# Teensy4-CANTool-Rev3.net
KiCad netlist of a schematic drawn in Altium Designer
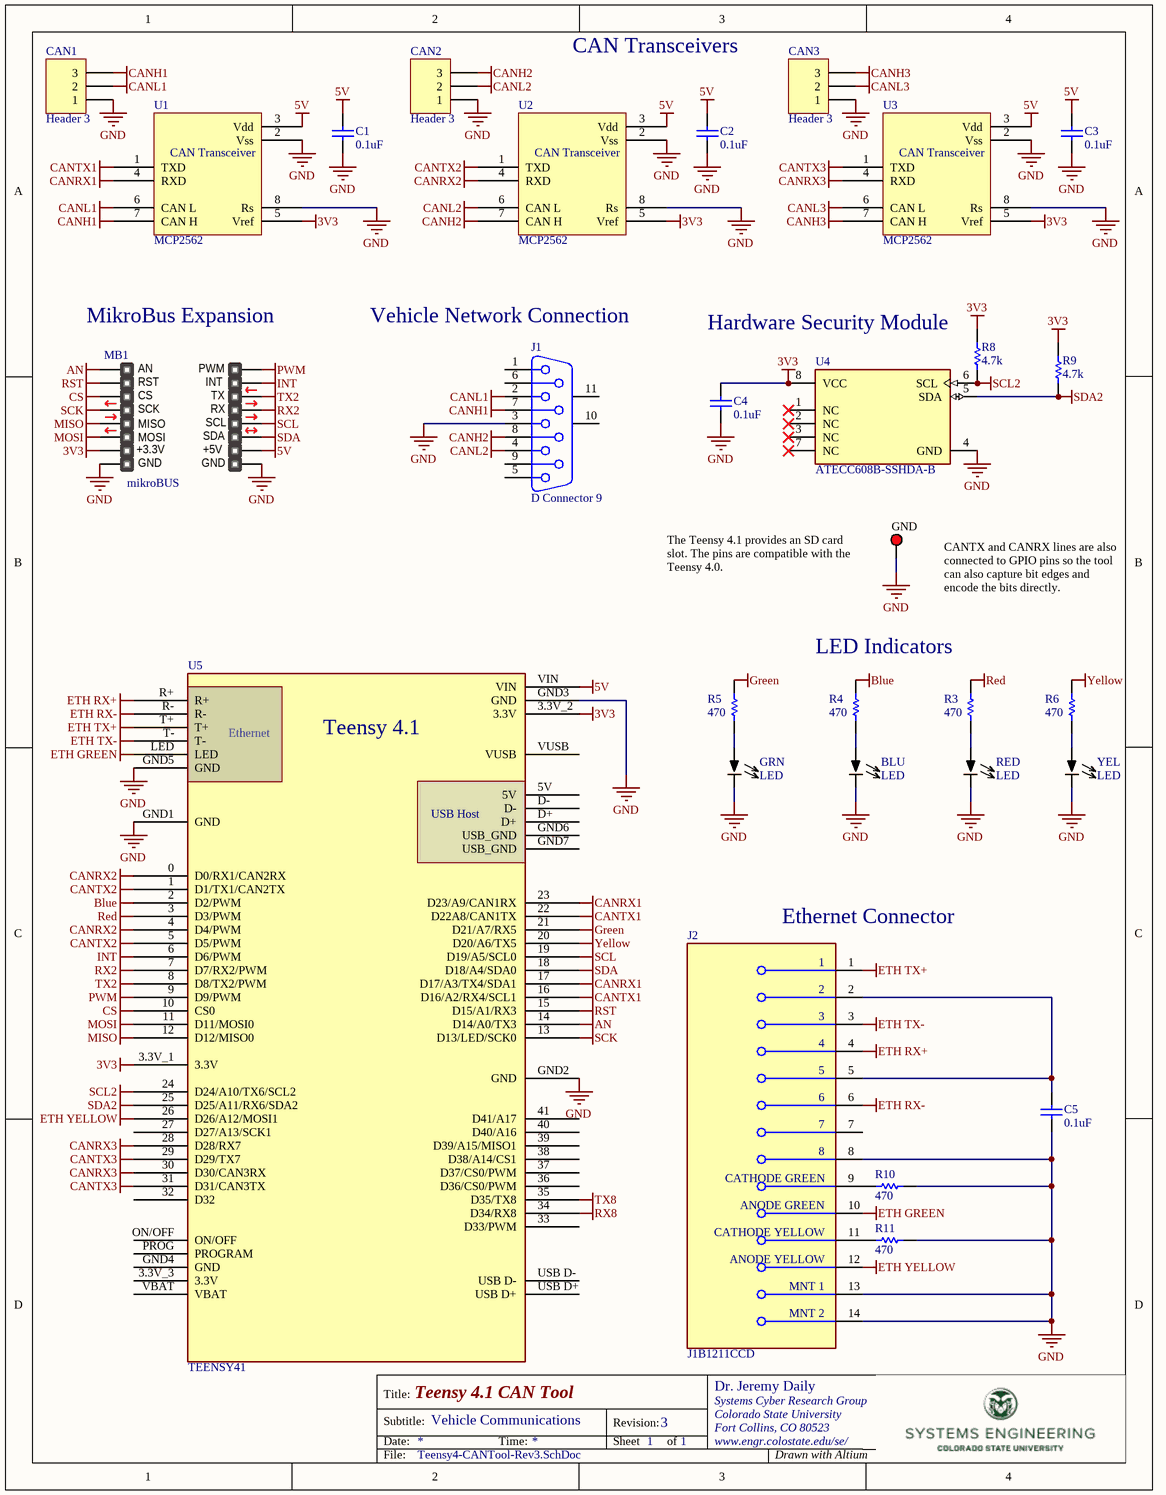
[diagram p0: Teensy4-CANTool-Rev3.SchDoc]

(export (version "E")
  (design (tool "Eeschema 10.0.6"))
  (components
    (comp (ref "BLU")
      (value "LED")
      (footprint "LED - 5mm Through Hole")
      (description "Blue 470nm LED Indication - Discrete 3.2V Radial")
      (fields (field (name "MANUFACTURER") "Würth Elektronik") (field (name "PARTNUMBER") "151051BS04000"))
      (libsource (lib "Custom Parts") (part "LED"))
    )
    (comp (ref "C1")
      (value "0.1uF")
      (footprint "CAPR5-4X5")
      (description "0.1µF ±10% 50V Ceramic Capacitor X7R 0603 (1608 Metric)")
      (fields
        (field (name "MANUFACTURER") "Vishay Beyschlag/Draloric/BC Components")
        (field (name "PARTNUMBER") "K104K15X7RF53H5")
      )
      (libsource (lib "SSS Schematic Library") (part "Cap"))
    )
    (comp (ref "C2")
      (value "0.1uF")
      (footprint "CAPR5-4X5")
      (description "0.1µF ±10% 50V Ceramic Capacitor X7R 0603 (1608 Metric)")
      (fields
        (field (name "MANUFACTURER") "Vishay Beyschlag/Draloric/BC Components")
        (field (name "PARTNUMBER") "K104K15X7RF53H5")
      )
      (libsource (lib "SSS Schematic Library") (part "Cap"))
    )
    (comp (ref "C3")
      (value "0.1uF")
      (footprint "CAPR5-4X5")
      (description "0.1µF ±10% 50V Ceramic Capacitor X7R 0603 (1608 Metric)")
      (fields
        (field (name "MANUFACTURER") "Vishay Beyschlag/Draloric/BC Components")
        (field (name "PARTNUMBER") "K104K15X7RF53H5")
      )
      (libsource (lib "SSS Schematic Library") (part "Cap"))
    )
    (comp (ref "C4")
      (value "0.1uF")
      (footprint "CAPR5-4X5")
      (description "0.1µF ±10% 50V Ceramic Capacitor X7R 0603 (1608 Metric)")
      (fields
        (field (name "MANUFACTURER") "Vishay Beyschlag/Draloric/BC Components")
        (field (name "PARTNUMBER") "K104K15X7RF53H5")
      )
      (libsource (lib "SSS Schematic Library") (part "Cap"))
    )
    (comp (ref "C5")
      (value "0.1uF")
      (footprint "CAPR5-4X5")
      (description "0.1µF ±10% 50V Ceramic Capacitor X7R 0603 (1608 Metric)")
      (fields
        (field (name "MANUFACTURER") "Vishay Beyschlag/Draloric/BC Components")
        (field (name "PARTNUMBER") "K104K15X7RF53H5")
      )
      (libsource (lib "SSS Schematic Library") (part "Cap"))
    )
    (comp (ref "CAN1")
      (value "Header 3")
      (footprint "PCB Terminal Block - 3")
      (description "Header, 3-Pin")
      (fields (field (name "MANUFACTURER") "Phoenix Contact") (field (name "PARTNUMBER") "1935174"))
      (libsource (lib "Miscellaneous Connectors") (part "Header 3"))
    )
    (comp (ref "CAN2")
      (value "Header 3")
      (footprint "PCB Terminal Block - 3")
      (description "Header, 3-Pin")
      (fields (field (name "MANUFACTURER") "Phoenix Contact") (field (name "PARTNUMBER") "1935174"))
      (libsource (lib "Miscellaneous Connectors") (part "Header 3"))
    )
    (comp (ref "CAN3")
      (value "Header 3")
      (footprint "PCB Terminal Block - 3")
      (description "Header, 3-Pin")
      (fields (field (name "MANUFACTURER") "Phoenix Contact") (field (name "PARTNUMBER") "1935174"))
      (libsource (lib "Miscellaneous Connectors") (part "Header 3"))
    )
    (comp (ref "GND")
      (value "5010")
      (footprint "KSTN-5010_V")
      (description "Interconnection Device")
      (libsource (lib "CSU Systems Cyber") (part "TESTPOINT_RED"))
    )
    (comp (ref "GRN")
      (value "LED")
      (footprint "LED - 5mm Through Hole")
      (description "Green 572nm LED Indication - Discrete 2.1V Radial")
      (fields (field (name "MANUFACTURER") "Würth Elektronik") (field (name "PARTNUMBER") "151051VS04000"))
      (libsource (lib "Custom Parts") (part "LED"))
    )
    (comp (ref "J1")
      (value "D Connector 9")
      (footprint "DSUB1.385-2H9")
      (description "CONN D-SUB PLUG 9POS R/A SLDR")
      (fields
        (field (name "MANUFACTURER") "Assmann WSW Components")
        (field (name "PARTNUMBER") "A-DS 09 A/KG-T2S")
      )
      (libsource (lib "Miscellaneous Connectors") (part "D Connector 9"))
    )
    (comp (ref "J2")
      (value "J1B1211CCD")
      (footprint "FP-J1B1211CCD-MFG")
      (description "CONN JACK 1PORT 100 BASE-T PCB")
      (libsource (lib "Altium Content Vault") (part "043a9053fb366fe6dc2bf5dbfb72c80"))
    )
    (comp (ref "MB1")
      (value "mikroBUS")
      (footprint "mikroBUS - Midi")
      (description "mikroBUS compatible add-on board")
      (libsource (lib "mikroBUS_Add-on_standard") (part "mikroBUS compatible add-on board"))
    )
    (comp (ref "R3")
      (value "470")
      (footprint "AXIAL-0.4")
      (description "470 Ohms ±5% 0.25W, 1/4W Through Hole Resistor Axial Carbon Film")
      (fields (field (name "MANUFACTURER") "YAGEO") (field (name "PARTNUMBER") "CFR-25JB-52-470R"))
      (libsource (lib "Miscellaneous Devices") (part "Res1"))
    )
    (comp (ref "R4")
      (value "470")
      (footprint "AXIAL-0.4")
      (description "470 Ohms ±5% 0.25W, 1/4W Through Hole Resistor Axial Carbon Film")
      (fields (field (name "MANUFACTURER") "YAGEO") (field (name "PARTNUMBER") "CFR-25JB-52-470R"))
      (libsource (lib "Miscellaneous Devices") (part "Res1"))
    )
    (comp (ref "R5")
      (value "470")
      (footprint "AXIAL-0.4")
      (description "470 Ohms ±5% 0.25W, 1/4W Through Hole Resistor Axial Carbon Film")
      (fields (field (name "MANUFACTURER") "YAGEO") (field (name "PARTNUMBER") "CFR-25JB-52-470R"))
      (libsource (lib "Miscellaneous Devices") (part "Res1"))
    )
    (comp (ref "R6")
      (value "470")
      (footprint "AXIAL-0.4")
      (description "470 Ohms ±5% 0.25W, 1/4W Through Hole Resistor Axial Carbon Film")
      (fields (field (name "MANUFACTURER") "YAGEO") (field (name "PARTNUMBER") "CFR-25JB-52-470R"))
      (libsource (lib "Miscellaneous Devices") (part "Res1"))
    )
    (comp (ref "R8")
      (value "4.7k")
      (footprint "RESA60-630X240")
      (description "Axial Resistor, 47.5 KOhm, +/- 1%, 0.25 W, -55 to 155 degC, 2-Pin THD, RoHS, Bulk")
      (fields (field (name "TOLERANCE") "20%"))
      (libsource (lib "Altium Content Vault") (part "RES-2"))
    )
    (comp (ref "R9")
      (value "4.7k")
      (footprint "RESA60-630X240")
      (description "Axial Resistor, 47.5 KOhm, +/- 1%, 0.25 W, -55 to 155 degC, 2-Pin THD, RoHS, Bulk")
      (fields (field (name "TOLERANCE") "20%"))
      (libsource (lib "Altium Content Vault") (part "RES-2"))
    )
    (comp (ref "R10")
      (value "470")
      (footprint "AXIAL-0.4")
      (description "470 Ohms ±5% 0.25W, 1/4W Through Hole Resistor Axial Carbon Film")
      (fields (field (name "MANUFACTURER") "YAGEO") (field (name "PARTNUMBER") "CFR-25JB-52-470R"))
      (libsource (lib "Miscellaneous Devices") (part "Res1"))
    )
    (comp (ref "R11")
      (value "470")
      (footprint "axial-0.4")
      (description "470 Ohms ±5% 0.25W, 1/4W Through Hole Resistor Axial Carbon Film")
      (fields (field (name "MANUFACTURER") "YAGEO") (field (name "PARTNUMBER") "CFR-25JB-52-470R"))
      (libsource (lib "Miscellaneous Devices") (part "Res1"))
    )
    (comp (ref "RED")
      (value "LED")
      (footprint "LED - 5mm Through Hole")
      (description "Red 645nm LED Indication - Discrete 2.1V Radial")
      (fields (field (name "MANUFACTURER") "Würth Elektronik") (field (name "PARTNUMBER") "151051RS11000"))
      (libsource (lib "Custom Parts") (part "LED"))
    )
    (comp (ref "U1")
      (value "MCP2562")
      (footprint "DIP8")
      (description "1/1 Transceiver CANbus 8-PDIP")
      (fields
        (field (name "MANUFACTURER") "Microchip Technology")
        (field (name "PARTNUMBER") "MCP2562FD-E/P")
      )
      (libsource (lib "SSS Integrated Library") (part "MCP2551"))
    )
    (comp (ref "U2")
      (value "MCP2562")
      (footprint "DIP8")
      (description "1/1 Transceiver CANbus 8-PDIP")
      (fields
        (field (name "MANUFACTURER") "Microchip Technology")
        (field (name "PARTNUMBER") "MCP2562FD-E/P")
      )
      (libsource (lib "SSS Integrated Library") (part "MCP2551"))
    )
    (comp (ref "U3")
      (value "MCP2562")
      (footprint "DIP8")
      (description "1/1 Transceiver CANbus 8-PDIP")
      (fields
        (field (name "MANUFACTURER") "Microchip Technology")
        (field (name "PARTNUMBER") "MCP2562FD-E/P")
      )
      (libsource (lib "SSS Integrated Library") (part "MCP2551"))
    )
    (comp (ref "U4")
      (value "ATECC608B-SSHDA-B")
      (footprint "FP-C04-057-SWB-IPC_C")
      (description "IC AUTHENTICATION CHIP")
      (libsource (lib "Altium Content Vault") (part "1f7132c691f143be83197a8e1c9b4e2"))
    )
    (comp (ref "U5")
      (value "TEENSY41")
      (footprint "MODULE_DEV-16771")
      (description "PJRC Teensy 4.1 Development Board")
      (libsource (lib "CSU Systems Cyber") (part "Teensy 4.1"))
    )
    (comp (ref "YEL")
      (value "LED")
      (footprint "LED - 5mm Through Hole")
      (description "Yellow 590nm LED Indication - Discrete 2V Radial")
      (fields (field (name "MANUFACTURER") "Würth Elektronik") (field (name "PARTNUMBER") "151051YS04000"))
      (libsource (lib "Custom Parts") (part "LED"))
    )
  )
  (nets
    (net (code "1") (name "3V3") (class "Default")
      (node (ref "C4") (pin "2") (pinfunction "2_2") (pintype "passive"))
      (node (ref "MB1") (pin "7") (pinfunction "3.3V_7") (pintype "passive"))
      (node (ref "R8") (pin "2") (pinfunction "2_2") (pintype "passive"))
      (node (ref "R9") (pin "2") (pinfunction "2_2") (pintype "passive"))
      (node (ref "U1") (pin "5") (pinfunction "Vref_5") (pintype "passive"))
      (node (ref "U2") (pin "5") (pinfunction "Vref_5") (pintype "passive"))
      (node (ref "U3") (pin "5") (pinfunction "Vref_5") (pintype "passive"))
      (node (ref "U4") (pin "8") (pinfunction "VCC_8") (pintype "power_in"))
      (node (ref "U5") (pin "3.3V_1") (pinfunction "3.3V_3.3V_1") (pintype "passive"))
      (node (ref "U5") (pin "3.3V_2") (pinfunction "3.3V_3.3V_2") (pintype "power_in"))
    )
    (net (code "2") (name "5V") (class "Default")
      (node (ref "C1") (pin "2") (pinfunction "2_2") (pintype "passive"))
      (node (ref "C2") (pin "2") (pinfunction "2_2") (pintype "passive"))
      (node (ref "C3") (pin "2") (pinfunction "2_2") (pintype "passive"))
      (node (ref "MB1") (pin "10") (pinfunction "5V_10") (pintype "passive"))
      (node (ref "U1") (pin "3") (pinfunction "Vdd_3") (pintype "passive"))
      (node (ref "U2") (pin "3") (pinfunction "Vdd_3") (pintype "passive"))
      (node (ref "U3") (pin "3") (pinfunction "Vdd_3") (pintype "passive"))
      (node (ref "U5") (pin "VIN") (pinfunction "VIN_VIN") (pintype "passive"))
    )
    (net (code "3") (name "AN") (class "Default")
      (node (ref "MB1") (pin "1") (pinfunction "AN_1") (pintype "passive"))
      (node (ref "U5") (pin "14") (pinfunction "D14/A0/TX3_14") (pintype "passive"))
    )
    (net (code "4") (name "Blue") (class "Default")
      (node (ref "R4") (pin "2") (pinfunction "2_2") (pintype "passive"))
      (node (ref "U5") (pin "2") (pinfunction "D2/PWM_2") (pintype "passive"))
    )
    (net (code "5") (name "CANH1") (class "Default")
      (node (ref "CAN1") (pin "3") (pinfunction "3_3") (pintype "passive"))
      (node (ref "J1") (pin "7") (pinfunction "7_7") (pintype "passive"))
      (node (ref "U1") (pin "7") (pinfunction "CAN_H_7") (pintype "passive"))
    )
    (net (code "6") (name "CANH2") (class "Default")
      (node (ref "CAN2") (pin "3") (pinfunction "3_3") (pintype "passive"))
      (node (ref "J1") (pin "8") (pinfunction "8_8") (pintype "passive"))
      (node (ref "U2") (pin "7") (pinfunction "CAN_H_7") (pintype "passive"))
    )
    (net (code "7") (name "CANH3") (class "Default")
      (node (ref "CAN3") (pin "3") (pinfunction "3_3") (pintype "passive"))
      (node (ref "U3") (pin "7") (pinfunction "CAN_H_7") (pintype "passive"))
    )
    (net (code "8") (name "CANL1") (class "Default")
      (node (ref "CAN1") (pin "2") (pinfunction "2_2") (pintype "passive"))
      (node (ref "J1") (pin "2") (pinfunction "2_2") (pintype "passive"))
      (node (ref "U1") (pin "6") (pinfunction "CAN_L_6") (pintype "passive"))
    )
    (net (code "9") (name "CANL2") (class "Default")
      (node (ref "CAN2") (pin "2") (pinfunction "2_2") (pintype "passive"))
      (node (ref "J1") (pin "4") (pinfunction "4_4") (pintype "passive"))
      (node (ref "U2") (pin "6") (pinfunction "CAN_L_6") (pintype "passive"))
    )
    (net (code "10") (name "CANL3") (class "Default")
      (node (ref "CAN3") (pin "2") (pinfunction "2_2") (pintype "passive"))
      (node (ref "U3") (pin "6") (pinfunction "CAN_L_6") (pintype "passive"))
    )
    (net (code "11") (name "CANRX1") (class "Default")
      (node (ref "U1") (pin "4") (pinfunction "RXD_4") (pintype "passive"))
      (node (ref "U5") (pin "17") (pinfunction "D17/A3/TX4/SDA1_17") (pintype "passive"))
      (node (ref "U5") (pin "23") (pinfunction "D23/A9/CAN1RX_23") (pintype "passive"))
    )
    (net (code "12") (name "CANRX2") (class "Default")
      (node (ref "U2") (pin "4") (pinfunction "RXD_4") (pintype "passive"))
      (node (ref "U5") (pin "0") (pinfunction "D0/RX1/CAN2RX_0") (pintype "passive"))
      (node (ref "U5") (pin "4") (pinfunction "D4/PWM_4") (pintype "passive"))
    )
    (net (code "13") (name "CANRX3") (class "Default")
      (node (ref "U3") (pin "4") (pinfunction "RXD_4") (pintype "passive"))
      (node (ref "U5") (pin "28") (pinfunction "D28/RX7_28") (pintype "passive"))
      (node (ref "U5") (pin "30") (pinfunction "D30/CAN3RX_30") (pintype "passive"))
    )
    (net (code "14") (name "CANTX1") (class "Default")
      (node (ref "U1") (pin "1") (pinfunction "TXD_1") (pintype "passive"))
      (node (ref "U5") (pin "16") (pinfunction "D16/A2/RX4/SCL1_16") (pintype "passive"))
      (node (ref "U5") (pin "22") (pinfunction "D22A8/CAN1TX_22") (pintype "passive"))
    )
    (net (code "15") (name "CANTX2") (class "Default")
      (node (ref "U2") (pin "1") (pinfunction "TXD_1") (pintype "passive"))
      (node (ref "U5") (pin "1") (pinfunction "D1/TX1/CAN2TX_1") (pintype "passive"))
      (node (ref "U5") (pin "5") (pinfunction "D5/PWM_5") (pintype "passive"))
    )
    (net (code "16") (name "CANTX3") (class "Default")
      (node (ref "U3") (pin "1") (pinfunction "TXD_1") (pintype "passive"))
      (node (ref "U5") (pin "29") (pinfunction "D29/TX7_29") (pintype "passive"))
      (node (ref "U5") (pin "31") (pinfunction "D31/CAN3TX_31") (pintype "passive"))
    )
    (net (code "17") (name "CS") (class "Default")
      (node (ref "MB1") (pin "3") (pinfunction "CS_3") (pintype "passive"))
      (node (ref "U5") (pin "10") (pinfunction "CS0_10") (pintype "passive"))
    )
    (net (code "18") (name "ETH GREEN") (class "Default")
      (node (ref "J2") (pin "10") (pinfunction "ANODE_GREEN_10") (pintype "passive"))
      (node (ref "U5") (pin "LED") (pinfunction "LED_LED") (pintype "passive"))
    )
    (net (code "19") (name "ETH RX+") (class "Default")
      (node (ref "J2") (pin "4") (pinfunction "4_4") (pintype "passive"))
      (node (ref "U5") (pin "R+") (pinfunction "R+_R+") (pintype "passive"))
    )
    (net (code "20") (name "ETH RX-") (class "Default")
      (node (ref "J2") (pin "6") (pinfunction "6_6") (pintype "passive"))
      (node (ref "U5") (pin "R-") (pinfunction "R-_R-") (pintype "passive"))
    )
    (net (code "21") (name "ETH TX+") (class "Default")
      (node (ref "J2") (pin "1") (pinfunction "1_1") (pintype "passive"))
      (node (ref "U5") (pin "T+") (pinfunction "T+_T+") (pintype "passive"))
    )
    (net (code "22") (name "ETH TX-") (class "Default")
      (node (ref "J2") (pin "3") (pinfunction "3_3") (pintype "passive"))
      (node (ref "U5") (pin "T-") (pinfunction "T-_T-") (pintype "passive"))
    )
    (net (code "23") (name "ETH YELLOW") (class "Default")
      (node (ref "J2") (pin "12") (pinfunction "ANODE_YELLOW_12") (pintype "passive"))
      (node (ref "U5") (pin "26") (pinfunction "D26/A12/MOSI1_26") (pintype "passive"))
    )
    (net (code "24") (name "GND") (class "Default")
      (node (ref "BLU") (pin "2") (pinfunction "C_2") (pintype "passive"))
      (node (ref "C1") (pin "1") (pinfunction "1_1") (pintype "passive"))
      (node (ref "C2") (pin "1") (pinfunction "1_1") (pintype "passive"))
      (node (ref "C3") (pin "1") (pinfunction "1_1") (pintype "passive"))
      (node (ref "C4") (pin "1") (pinfunction "1_1") (pintype "passive"))
      (node (ref "C5") (pin "1") (pinfunction "1_1") (pintype "passive"))
      (node (ref "CAN1") (pin "1") (pinfunction "1_1") (pintype "passive"))
      (node (ref "CAN2") (pin "1") (pinfunction "1_1") (pintype "passive"))
      (node (ref "CAN3") (pin "1") (pinfunction "1_1") (pintype "passive"))
      (node (ref "GND") (pin "1") (pinfunction "1_1") (pintype "passive"))
      (node (ref "GRN") (pin "2") (pinfunction "C_2") (pintype "passive"))
      (node (ref "J1") (pin "3") (pinfunction "3_3") (pintype "passive"))
      (node (ref "J2") (pin "13") (pinfunction "MNT_1_13") (pintype "passive"))
      (node (ref "J2") (pin "14") (pinfunction "MNT_2_14") (pintype "passive"))
      (node (ref "J2") (pin "8") (pinfunction "8_8") (pintype "passive"))
      (node (ref "MB1") (pin "8") (pinfunction "GND_8") (pintype "passive"))
      (node (ref "MB1") (pin "9") (pinfunction "GND_9") (pintype "passive"))
      (node (ref "R10") (pin "1") (pinfunction "1_1") (pintype "passive"))
      (node (ref "R11") (pin "1") (pinfunction "1_1") (pintype "passive"))
      (node (ref "RED") (pin "2") (pinfunction "C_2") (pintype "passive"))
      (node (ref "U1") (pin "2") (pinfunction "Vss_2") (pintype "passive"))
      (node (ref "U1") (pin "8") (pinfunction "Rs_8") (pintype "passive"))
      (node (ref "U2") (pin "2") (pinfunction "Vss_2") (pintype "passive"))
      (node (ref "U2") (pin "8") (pinfunction "Rs_8") (pintype "passive"))
      (node (ref "U3") (pin "2") (pinfunction "Vss_2") (pintype "passive"))
      (node (ref "U3") (pin "8") (pinfunction "Rs_8") (pintype "passive"))
      (node (ref "U4") (pin "4") (pinfunction "GND_4") (pintype "power_in"))
      (node (ref "U5") (pin "GND1") (pinfunction "GND_GND1") (pintype "passive"))
      (node (ref "U5") (pin "GND2") (pinfunction "GND_GND2") (pintype "power_in"))
      (node (ref "U5") (pin "GND3") (pinfunction "GND_GND3") (pintype "power_in"))
      (node (ref "U5") (pin "GND5") (pinfunction "GND_GND5") (pintype "passive"))
      (node (ref "YEL") (pin "2") (pinfunction "C_2") (pintype "passive"))
    )
    (net (code "25") (name "Green") (class "Default")
      (node (ref "R5") (pin "2") (pinfunction "2_2") (pintype "passive"))
      (node (ref "U5") (pin "21") (pinfunction "D21/A7/RX5_21") (pintype "passive"))
    )
    (net (code "26") (name "INT") (class "Default")
      (node (ref "MB1") (pin "15") (pinfunction "INT_15") (pintype "passive"))
      (node (ref "U5") (pin "6") (pinfunction "D6/PWM_6") (pintype "passive"))
    )
    (net (code "27") (name "MISO") (class "Default")
      (node (ref "MB1") (pin "5") (pinfunction "MISO_5") (pintype "passive"))
      (node (ref "U5") (pin "12") (pinfunction "D12/MISO0_12") (pintype "passive"))
    )
    (net (code "28") (name "MOSI") (class "Default")
      (node (ref "MB1") (pin "6") (pinfunction "MOSI_6") (pintype "passive"))
      (node (ref "U5") (pin "11") (pinfunction "D11/MOSI0_11") (pintype "passive"))
    )
    (net (code "29") (name "Net-(BLU-A)") (class "Default")
      (node (ref "BLU") (pin "1") (pinfunction "A_1") (pintype "passive"))
      (node (ref "R4") (pin "1") (pinfunction "1_1") (pintype "passive"))
    )
    (net (code "30") (name "Net-(C5-Pad2)") (class "Default")
      (node (ref "C5") (pin "2") (pinfunction "2_2") (pintype "passive"))
      (node (ref "J2") (pin "2") (pinfunction "2_2") (pintype "passive"))
      (node (ref "J2") (pin "5") (pinfunction "5_5") (pintype "passive"))
    )
    (net (code "31") (name "Net-(GRN-A)") (class "Default")
      (node (ref "GRN") (pin "1") (pinfunction "A_1") (pintype "passive"))
      (node (ref "R5") (pin "1") (pinfunction "1_1") (pintype "passive"))
    )
    (net (code "32") (name "Net-(J2-CATHODE_GREEN)") (class "Default")
      (node (ref "J2") (pin "9") (pinfunction "CATHODE_GREEN_9") (pintype "passive"))
      (node (ref "R10") (pin "2") (pinfunction "2_2") (pintype "passive"))
    )
    (net (code "33") (name "Net-(J2-CATHODE_YELLOW)") (class "Default")
      (node (ref "J2") (pin "11") (pinfunction "CATHODE_YELLOW_11") (pintype "passive"))
      (node (ref "R11") (pin "2") (pinfunction "2_2") (pintype "passive"))
    )
    (net (code "34") (name "Net-(RED-A)") (class "Default")
      (node (ref "R3") (pin "1") (pinfunction "1_1") (pintype "passive"))
      (node (ref "RED") (pin "1") (pinfunction "A_1") (pintype "passive"))
    )
    (net (code "35") (name "Net-(YEL-A)") (class "Default")
      (node (ref "R6") (pin "1") (pinfunction "1_1") (pintype "passive"))
      (node (ref "YEL") (pin "1") (pinfunction "A_1") (pintype "passive"))
    )
    (net (code "36") (name "PWM") (class "Default")
      (node (ref "MB1") (pin "16") (pinfunction "PWM_16") (pintype "passive"))
      (node (ref "U5") (pin "9") (pinfunction "D9/PWM_9") (pintype "passive"))
    )
    (net (code "37") (name "RST") (class "Default")
      (node (ref "MB1") (pin "2") (pinfunction "RST_2") (pintype "passive"))
      (node (ref "U5") (pin "15") (pinfunction "D15/A1/RX3_15") (pintype "passive"))
    )
    (net (code "38") (name "RX2") (class "Default")
      (node (ref "MB1") (pin "13") (pinfunction "TX_13") (pintype "passive"))
      (node (ref "U5") (pin "7") (pinfunction "D7/RX2/PWM_7") (pintype "passive"))
    )
    (net (code "39") (name "RX8") (class "Default")
      (node (ref "U5") (pin "34") (pinfunction "D34/RX8_34") (pintype "passive"))
    )
    (net (code "40") (name "Red") (class "Default")
      (node (ref "R3") (pin "2") (pinfunction "2_2") (pintype "passive"))
      (node (ref "U5") (pin "3") (pinfunction "D3/PWM_3") (pintype "passive"))
    )
    (net (code "41") (name "SCK") (class "Default")
      (node (ref "MB1") (pin "4") (pinfunction "SCK_4") (pintype "passive"))
      (node (ref "U5") (pin "13") (pinfunction "D13/LED/SCK0_13") (pintype "passive"))
    )
    (net (code "42") (name "SCL") (class "Default")
      (node (ref "MB1") (pin "12") (pinfunction "SCL_12") (pintype "passive"))
      (node (ref "U5") (pin "19") (pinfunction "D19/A5/SCL0_19") (pintype "passive"))
    )
    (net (code "43") (name "SCL2") (class "Default")
      (node (ref "R8") (pin "1") (pinfunction "1_1") (pintype "passive"))
      (node (ref "U4") (pin "6") (pinfunction "SCL_6") (pintype "input"))
      (node (ref "U5") (pin "24") (pinfunction "D24/A10/TX6/SCL2_24") (pintype "passive"))
    )
    (net (code "44") (name "SDA") (class "Default")
      (node (ref "MB1") (pin "11") (pinfunction "SDA_11") (pintype "passive"))
      (node (ref "U5") (pin "18") (pinfunction "D18/A4/SDA0_18") (pintype "passive"))
    )
    (net (code "45") (name "SDA2") (class "Default")
      (node (ref "R9") (pin "1") (pinfunction "1_1") (pintype "passive"))
      (node (ref "U4") (pin "5") (pinfunction "SDA_5") (pintype "bidirectional"))
      (node (ref "U5") (pin "25") (pinfunction "D25/A11/RX6/SDA2_25") (pintype "passive"))
    )
    (net (code "46") (name "TX2") (class "Default")
      (node (ref "MB1") (pin "14") (pinfunction "RX_14") (pintype "passive"))
      (node (ref "U5") (pin "8") (pinfunction "D8/TX2/PWM_8") (pintype "passive"))
    )
    (net (code "47") (name "TX8") (class "Default")
      (node (ref "U5") (pin "35") (pinfunction "D35/TX8_35") (pintype "passive"))
    )
    (net (code "48") (name "Yellow") (class "Default")
      (node (ref "R6") (pin "2") (pinfunction "2_2") (pintype "passive"))
      (node (ref "U5") (pin "20") (pinfunction "D20/A6/TX5_20") (pintype "passive"))
    )
    (net (code "49") (name "unconnected-(J1-MH1-Pad10)") (class "Default")
      (node (ref "J1") (pin "10") (pinfunction "MH1_10") (pintype "passive"))
    )
    (net (code "50") (name "unconnected-(J1-MH2-Pad11)") (class "Default")
      (node (ref "J1") (pin "11") (pinfunction "MH2_11") (pintype "passive"))
    )
    (net (code "51") (name "unconnected-(J1-Pad1)") (class "Default")
      (node (ref "J1") (pin "1") (pinfunction "1_1") (pintype "passive"))
    )
    (net (code "52") (name "unconnected-(J1-Pad5)") (class "Default")
      (node (ref "J1") (pin "5") (pinfunction "5_5") (pintype "passive"))
    )
    (net (code "53") (name "unconnected-(J1-Pad6)") (class "Default")
      (node (ref "J1") (pin "6") (pinfunction "6_6") (pintype "passive"))
    )
    (net (code "54") (name "unconnected-(J1-Pad9)") (class "Default")
      (node (ref "J1") (pin "9") (pinfunction "9_9") (pintype "passive"))
    )
    (net (code "55") (name "unconnected-(J2-Pad7)") (class "Default")
      (node (ref "J2") (pin "7") (pinfunction "7_7") (pintype "passive"))
    )
    (net (code "56") (name "unconnected-(U4-NC-Pad1)") (class "Default")
      (node (ref "U4") (pin "1") (pinfunction "NC_1") (pintype "passive+no_connect"))
    )
    (net (code "57") (name "unconnected-(U4-NC-Pad2)") (class "Default")
      (node (ref "U4") (pin "2") (pinfunction "NC_2") (pintype "passive+no_connect"))
    )
    (net (code "58") (name "unconnected-(U4-NC-Pad3)") (class "Default")
      (node (ref "U4") (pin "3") (pinfunction "NC_3") (pintype "passive+no_connect"))
    )
    (net (code "59") (name "unconnected-(U4-NC-Pad7)") (class "Default")
      (node (ref "U4") (pin "7") (pinfunction "NC_7") (pintype "passive+no_connect"))
    )
    (net (code "60") (name "unconnected-(U5-3.3V-Pad3.3V_3)") (class "Default")
      (node (ref "U5") (pin "3.3V_3") (pinfunction "3.3V_3.3V_3") (pintype "passive"))
    )
    (net (code "61") (name "unconnected-(U5-D27{slash}A13{slash}SCK1-Pad27)") (class "Default")
      (node (ref "U5") (pin "27") (pinfunction "D27/A13/SCK1_27") (pintype "passive"))
    )
    (net (code "62") (name "unconnected-(U5-D32-Pad32)") (class "Default")
      (node (ref "U5") (pin "32") (pinfunction "D32_32") (pintype "passive"))
    )
    (net (code "63") (name "unconnected-(U5-D33{slash}PWM-Pad33)") (class "Default")
      (node (ref "U5") (pin "33") (pinfunction "D33/PWM_33") (pintype "passive"))
    )
    (net (code "64") (name "unconnected-(U5-D36{slash}CS0{slash}PWM-Pad36)") (class "Default")
      (node (ref "U5") (pin "36") (pinfunction "D36/CS0/PWM_36") (pintype "passive"))
    )
    (net (code "65") (name "unconnected-(U5-D37{slash}CS0{slash}PWM-Pad37)") (class "Default")
      (node (ref "U5") (pin "37") (pinfunction "D37/CS0/PWM_37") (pintype "passive"))
    )
    (net (code "66") (name "unconnected-(U5-D38{slash}A14{slash}CS1-Pad38)") (class "Default")
      (node (ref "U5") (pin "38") (pinfunction "D38/A14/CS1_38") (pintype "passive"))
    )
    (net (code "67") (name "unconnected-(U5-D39{slash}A15{slash}MISO1-Pad39)") (class "Default")
      (node (ref "U5") (pin "39") (pinfunction "D39/A15/MISO1_39") (pintype "passive"))
    )
    (net (code "68") (name "unconnected-(U5-D40{slash}A16-Pad40)") (class "Default")
      (node (ref "U5") (pin "40") (pinfunction "D40/A16_40") (pintype "passive"))
    )
    (net (code "69") (name "unconnected-(U5-D41{slash}A17-Pad41)") (class "Default")
      (node (ref "U5") (pin "41") (pinfunction "D41/A17_41") (pintype "passive"))
    )
    (net (code "70") (name "unconnected-(U5-GND-PadGND4)") (class "Default")
      (node (ref "U5") (pin "GND4") (pinfunction "GND_GND4") (pintype "passive"))
    )
    (net (code "71") (name "unconnected-(U5-PROGRAM-PadPROG)") (class "Default")
      (node (ref "U5") (pin "PROG") (pinfunction "PROGRAM_PROG") (pintype "passive"))
    )
    (net (code "72") (name "unconnected-(U5-Pad5V)") (class "Default")
      (node (ref "U5") (pin "5V") (pinfunction "5V_5V") (pintype "passive"))
    )
    (net (code "73") (name "unconnected-(U5-PadD+)") (class "Default")
      (node (ref "U5") (pin "D+") (pinfunction "D+_D+") (pintype "passive"))
    )
    (net (code "74") (name "unconnected-(U5-PadD-)") (class "Default")
      (node (ref "U5") (pin "D-") (pinfunction "D-_D-") (pintype "passive"))
    )
    (net (code "75") (name "unconnected-(U5-PadON{slash}OFF)") (class "Default")
      (node (ref "U5") (pin "ON/OFF") (pinfunction "ON/OFF_ON/OFF") (pintype "passive"))
    )
    (net (code "76") (name "unconnected-(U5-PadUSB_D+)") (class "Default")
      (node (ref "U5") (pin "USB_D+") (pinfunction "USB_D+_USB_D+") (pintype "passive"))
    )
    (net (code "77") (name "unconnected-(U5-PadUSB_D-)") (class "Default")
      (node (ref "U5") (pin "USB_D-") (pinfunction "USB_D-_USB_D-") (pintype "passive"))
    )
    (net (code "78") (name "unconnected-(U5-PadVBAT)") (class "Default")
      (node (ref "U5") (pin "VBAT") (pinfunction "VBAT_VBAT") (pintype "passive"))
    )
    (net (code "79") (name "unconnected-(U5-PadVUSB)") (class "Default")
      (node (ref "U5") (pin "VUSB") (pinfunction "VUSB_VUSB") (pintype "passive"))
    )
    (net (code "80") (name "unconnected-(U5-USB_GND-PadGND6)") (class "Default")
      (node (ref "U5") (pin "GND6") (pinfunction "USB_GND_GND6") (pintype "passive"))
    )
    (net (code "81") (name "unconnected-(U5-USB_GND-PadGND7)") (class "Default")
      (node (ref "U5") (pin "GND7") (pinfunction "USB_GND_GND7") (pintype "passive"))
    )
  )
)
